# MOSFET.net
KiCad netlist of a schematic drawn in Altium Designer
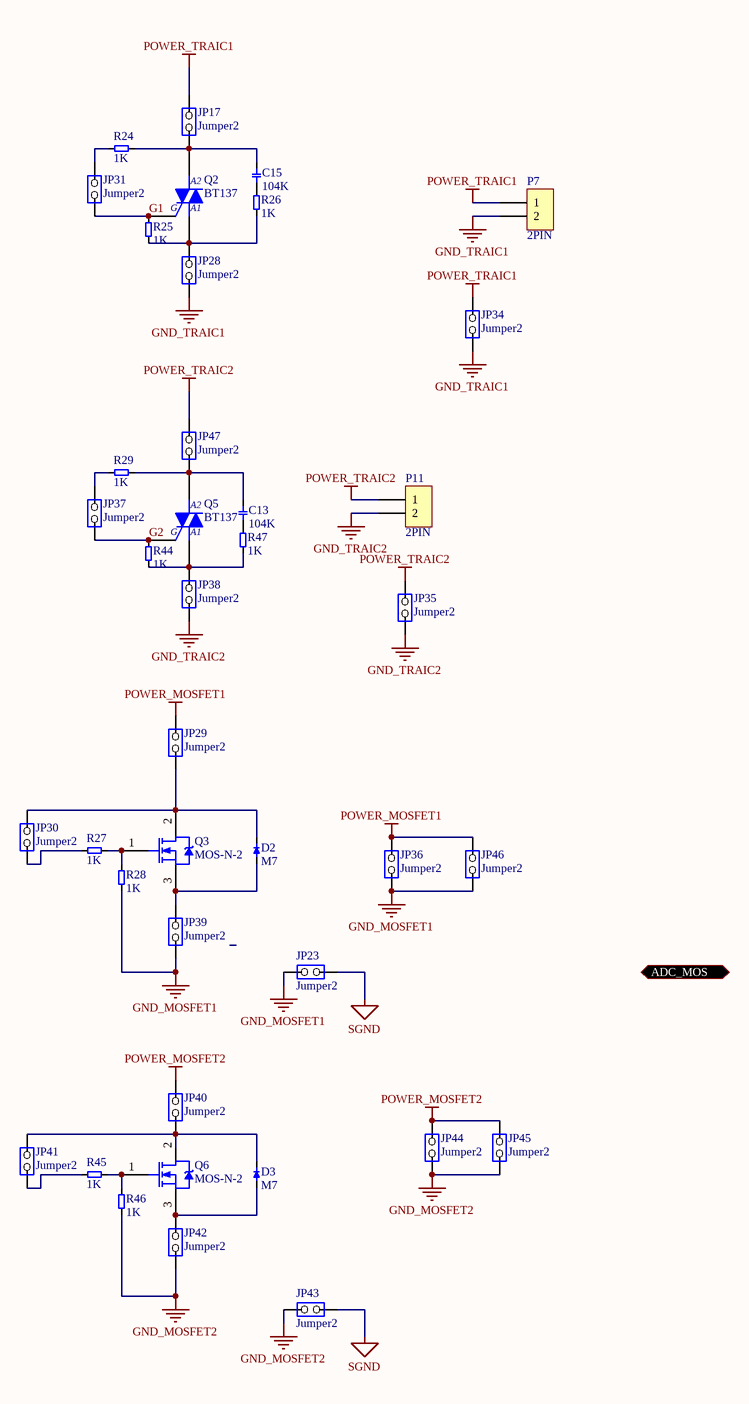
[diagram p0: 可控硅MOSFET.SchDoc]

(export (version "E")
  (design (tool "Eeschema 10.0.6"))
  (components
    (comp (ref "C13")
      (value "104K")
      (footprint "方形P15T6L18H12")
      (description "电容")
      (fields (field (name "PUBLISHER") "Altium Limited"))
      (libsource (lib "Miscellaneous Devices") (part "Cap"))
    )
    (comp (ref "C15")
      (value "104K")
      (footprint "方形P15T6L18H12")
      (description "电容")
      (fields (field (name "PUBLISHER") "Altium Limited"))
      (libsource (lib "Miscellaneous Devices") (part "Cap"))
    )
    (comp (ref "D2")
      (value "M7")
      (footprint "SMA")
      (description "二极管")
      (fields (field (name "PUBLISHER") "Altium Limited"))
      (libsource (lib "Miscellaneous Devices") (part "Diode"))
    )
    (comp (ref "D3")
      (value "M7")
      (footprint "SMA")
      (description "二极管")
      (fields (field (name "PUBLISHER") "Altium Limited"))
      (libsource (lib "Miscellaneous Devices") (part "Diode"))
    )
    (comp (ref "JP17")
      (value "Jumper2")
      (footprint "CON2-P2.54")
      (libsource (lib "Miscellaneous Connectors") (part "Jumper2"))
    )
    (comp (ref "JP23")
      (value "Jumper2")
      (footprint "CON2-P2.54")
      (libsource (lib "Miscellaneous Connectors") (part "Jumper2"))
    )
    (comp (ref "JP28")
      (value "Jumper2")
      (footprint "CON2-P2.54")
      (libsource (lib "Miscellaneous Connectors") (part "Jumper2"))
    )
    (comp (ref "JP29")
      (value "Jumper2")
      (footprint "CON2-P2.54")
      (libsource (lib "Miscellaneous Connectors") (part "Jumper2"))
    )
    (comp (ref "JP30")
      (value "Jumper2")
      (footprint "CON2-P2.54")
      (libsource (lib "Miscellaneous Connectors") (part "Jumper2"))
    )
    (comp (ref "JP31")
      (value "Jumper2")
      (footprint "CON2-P2.54")
      (libsource (lib "Miscellaneous Connectors") (part "Jumper2"))
    )
    (comp (ref "JP34")
      (value "Jumper2")
      (footprint "CON2-P2.54")
      (libsource (lib "Miscellaneous Connectors") (part "Jumper2"))
    )
    (comp (ref "JP35")
      (value "Jumper2")
      (footprint "CON2-P2.54")
      (libsource (lib "Miscellaneous Connectors") (part "Jumper2"))
    )
    (comp (ref "JP36")
      (value "Jumper2")
      (footprint "CON2-P2.54")
      (libsource (lib "Miscellaneous Connectors") (part "Jumper2"))
    )
    (comp (ref "JP37")
      (value "Jumper2")
      (footprint "CON2-P2.54")
      (libsource (lib "Miscellaneous Connectors") (part "Jumper2"))
    )
    (comp (ref "JP38")
      (value "Jumper2")
      (footprint "CON2-P2.54")
      (libsource (lib "Miscellaneous Connectors") (part "Jumper2"))
    )
    (comp (ref "JP39")
      (value "Jumper2")
      (footprint "CON2-P2.54")
      (libsource (lib "Miscellaneous Connectors") (part "Jumper2"))
    )
    (comp (ref "JP40")
      (value "Jumper2")
      (footprint "CON2-P2.54")
      (libsource (lib "Miscellaneous Connectors") (part "Jumper2"))
    )
    (comp (ref "JP41")
      (value "Jumper2")
      (footprint "CON2-P2.54")
      (libsource (lib "Miscellaneous Connectors") (part "Jumper2"))
    )
    (comp (ref "JP42")
      (value "Jumper2")
      (footprint "CON2-P2.54")
      (libsource (lib "Miscellaneous Connectors") (part "Jumper2"))
    )
    (comp (ref "JP43")
      (value "Jumper2")
      (footprint "CON2-P2.54")
      (libsource (lib "Miscellaneous Connectors") (part "Jumper2"))
    )
    (comp (ref "JP44")
      (value "Jumper2")
      (footprint "CON2-P2.54")
      (libsource (lib "Miscellaneous Connectors") (part "Jumper2"))
    )
    (comp (ref "JP45")
      (value "Jumper2")
      (footprint "CON2-P2.54")
      (libsource (lib "Miscellaneous Connectors") (part "Jumper2"))
    )
    (comp (ref "JP46")
      (value "Jumper2")
      (footprint "CON2-P2.54")
      (libsource (lib "Miscellaneous Connectors") (part "Jumper2"))
    )
    (comp (ref "JP47")
      (value "Jumper2")
      (footprint "CON2-P2.54")
      (libsource (lib "Miscellaneous Connectors") (part "Jumper2"))
    )
    (comp (ref "P7")
      (value "2PIN")
      (footprint "CON2-P3.96(VH)")
      (description "连接器")
      (fields (field (name "PUBLISHER") "Altium Limited"))
      (libsource (lib "Miscellaneous Connectors") (part "Header 2"))
    )
    (comp (ref "P11")
      (value "2PIN")
      (footprint "CON2-P3.96(VH)")
      (description "连接器")
      (fields (field (name "PUBLISHER") "Altium Limited"))
      (libsource (lib "Miscellaneous Connectors") (part "Header 2"))
    )
    (comp (ref "Q2")
      (value "BT137")
      (footprint "TO-252-2L")
      (description "可控硅")
      (fields (field (name "PUBLISHER") "Altium Limited"))
      (libsource (lib "Miscellaneous Devices") (part "Triac"))
    )
    (comp (ref "Q3")
      (value "MOS-N-2")
      (footprint "TO-252-2L")
      (description "N-Channel Power MOSFET")
      (fields (field (name "PUBLISHER") "Altium Limited"))
      (libsource (lib "Miscellaneous Devices") (part "MOS-N-2"))
    )
    (comp (ref "Q5")
      (value "BT137")
      (footprint "TO-252-2L")
      (description "可控硅")
      (fields (field (name "PUBLISHER") "Altium Limited"))
      (libsource (lib "Miscellaneous Devices") (part "Triac"))
    )
    (comp (ref "Q6")
      (value "MOS-N-2")
      (footprint "TO-252-2L")
      (description "N-Channel Power MOSFET")
      (fields (field (name "PUBLISHER") "Altium Limited"))
      (libsource (lib "Miscellaneous Devices") (part "MOS-N-2"))
    )
    (comp (ref "R24")
      (value "1K")
      (footprint "1206")
      (description "电阻")
      (fields (field (name "PUBLISHER") "Altium Limited"))
      (libsource (lib "Miscellaneous Devices") (part "Res1"))
    )
    (comp (ref "R25")
      (value "1K")
      (footprint "1206")
      (description "电阻")
      (fields (field (name "PUBLISHER") "Altium Limited"))
      (libsource (lib "Miscellaneous Devices") (part "Res1"))
    )
    (comp (ref "R26")
      (value "1K")
      (footprint "1206")
      (description "电阻")
      (fields (field (name "PUBLISHER") "Altium Limited"))
      (libsource (lib "Miscellaneous Devices") (part "Res1"))
    )
    (comp (ref "R27")
      (value "1K")
      (footprint "1206")
      (description "电阻")
      (fields (field (name "PUBLISHER") "Altium Limited"))
      (libsource (lib "Miscellaneous Devices") (part "Res1"))
    )
    (comp (ref "R28")
      (value "1K")
      (footprint "1206")
      (description "电阻")
      (fields (field (name "PUBLISHER") "Altium Limited"))
      (libsource (lib "Miscellaneous Devices") (part "Res1"))
    )
    (comp (ref "R29")
      (value "1K")
      (footprint "1206")
      (description "电阻")
      (fields (field (name "PUBLISHER") "Altium Limited"))
      (libsource (lib "Miscellaneous Devices") (part "Res1"))
    )
    (comp (ref "R44")
      (value "1K")
      (footprint "1206")
      (description "电阻")
      (fields (field (name "PUBLISHER") "Altium Limited"))
      (libsource (lib "Miscellaneous Devices") (part "Res1"))
    )
    (comp (ref "R45")
      (value "1K")
      (footprint "1206")
      (description "电阻")
      (fields (field (name "PUBLISHER") "Altium Limited"))
      (libsource (lib "Miscellaneous Devices") (part "Res1"))
    )
    (comp (ref "R46")
      (value "1K")
      (footprint "1206")
      (description "电阻")
      (fields (field (name "PUBLISHER") "Altium Limited"))
      (libsource (lib "Miscellaneous Devices") (part "Res1"))
    )
    (comp (ref "R47")
      (value "1K")
      (footprint "1206")
      (description "电阻")
      (fields (field (name "PUBLISHER") "Altium Limited"))
      (libsource (lib "Miscellaneous Devices") (part "Res1"))
    )
  )
  (nets
    (net (code "2") (name "/G1") (class "Default")
      (node (ref "JP31") (pin "1") (pinfunction "COMMON_1") (pintype "passive"))
      (node (ref "Q2") (pin "3") (pinfunction "G_3") (pintype "passive"))
      (node (ref "R25") (pin "2") (pinfunction "2_2") (pintype "passive"))
    )
    (net (code "3") (name "/G2") (class "Default")
      (node (ref "JP37") (pin "1") (pinfunction "COMMON_1") (pintype "passive"))
      (node (ref "Q5") (pin "3") (pinfunction "G_3") (pintype "passive"))
      (node (ref "R44") (pin "2") (pinfunction "2_2") (pintype "passive"))
    )
    (net (code "4") (name "GND_MOSFET1") (class "Default")
      (node (ref "JP23") (pin "2") (pinfunction "NO_2") (pintype "passive"))
      (node (ref "JP36") (pin "1") (pinfunction "COMMON_1") (pintype "passive"))
      (node (ref "JP39") (pin "1") (pinfunction "COMMON_1") (pintype "passive"))
      (node (ref "JP46") (pin "1") (pinfunction "COMMON_1") (pintype "passive"))
      (node (ref "R28") (pin "2") (pinfunction "2_2") (pintype "passive"))
    )
    (net (code "5") (name "GND_MOSFET2") (class "Default")
      (node (ref "JP42") (pin "1") (pinfunction "COMMON_1") (pintype "passive"))
      (node (ref "JP43") (pin "2") (pinfunction "NO_2") (pintype "passive"))
      (node (ref "JP44") (pin "1") (pinfunction "COMMON_1") (pintype "passive"))
      (node (ref "JP45") (pin "1") (pinfunction "COMMON_1") (pintype "passive"))
      (node (ref "R46") (pin "2") (pinfunction "2_2") (pintype "passive"))
    )
    (net (code "6") (name "GND_TRAIC1") (class "Default")
      (node (ref "JP28") (pin "1") (pinfunction "COMMON_1") (pintype "passive"))
      (node (ref "JP34") (pin "1") (pinfunction "COMMON_1") (pintype "passive"))
      (node (ref "P7") (pin "2") (pinfunction "2_2") (pintype "passive"))
    )
    (net (code "7") (name "GND_TRAIC2") (class "Default")
      (node (ref "JP35") (pin "1") (pinfunction "COMMON_1") (pintype "passive"))
      (node (ref "JP38") (pin "1") (pinfunction "COMMON_1") (pintype "passive"))
      (node (ref "P11") (pin "2") (pinfunction "2_2") (pintype "passive"))
    )
    (net (code "8") (name "Net-(C13-Pad1)") (class "Default")
      (node (ref "C13") (pin "1") (pinfunction "1_1") (pintype "passive"))
      (node (ref "R47") (pin "2") (pinfunction "2_2") (pintype "passive"))
    )
    (net (code "9") (name "Net-(C15-Pad1)") (class "Default")
      (node (ref "C15") (pin "1") (pinfunction "1_1") (pintype "passive"))
      (node (ref "R26") (pin "2") (pinfunction "2_2") (pintype "passive"))
    )
    (net (code "10") (name "Net-(JP17-COMMON)") (class "Default")
      (node (ref "C15") (pin "2") (pinfunction "2_2") (pintype "passive"))
      (node (ref "JP17") (pin "1") (pinfunction "COMMON_1") (pintype "passive"))
      (node (ref "Q2") (pin "2") (pinfunction "A2_2") (pintype "passive"))
      (node (ref "R24") (pin "2") (pinfunction "2_2") (pintype "passive"))
    )
    (net (code "11") (name "Net-(JP28-NO)") (class "Default")
      (node (ref "JP28") (pin "2") (pinfunction "NO_2") (pintype "passive"))
      (node (ref "Q2") (pin "1") (pinfunction "A1_1") (pintype "passive"))
      (node (ref "R25") (pin "1") (pinfunction "1_1") (pintype "passive"))
      (node (ref "R26") (pin "1") (pinfunction "1_1") (pintype "passive"))
    )
    (net (code "12") (name "Net-(JP29-COMMON)") (class "Default")
      (node (ref "D2") (pin "1") (pinfunction "1_1") (pintype "passive"))
      (node (ref "JP29") (pin "1") (pinfunction "COMMON_1") (pintype "passive"))
      (node (ref "JP30") (pin "2") (pinfunction "NO_2") (pintype "passive"))
      (node (ref "Q3") (pin "2") (pinfunction "D_2") (pintype "passive"))
    )
    (net (code "13") (name "Net-(JP30-COMMON)") (class "Default")
      (node (ref "JP30") (pin "1") (pinfunction "COMMON_1") (pintype "passive"))
      (node (ref "R27") (pin "2") (pinfunction "2_2") (pintype "passive"))
    )
    (net (code "14") (name "Net-(JP31-NO)") (class "Default")
      (node (ref "JP31") (pin "2") (pinfunction "NO_2") (pintype "passive"))
      (node (ref "R24") (pin "1") (pinfunction "1_1") (pintype "passive"))
    )
    (net (code "15") (name "Net-(JP37-NO)") (class "Default")
      (node (ref "JP37") (pin "2") (pinfunction "NO_2") (pintype "passive"))
      (node (ref "R29") (pin "1") (pinfunction "1_1") (pintype "passive"))
    )
    (net (code "16") (name "Net-(JP38-NO)") (class "Default")
      (node (ref "JP38") (pin "2") (pinfunction "NO_2") (pintype "passive"))
      (node (ref "Q5") (pin "1") (pinfunction "A1_1") (pintype "passive"))
      (node (ref "R44") (pin "1") (pinfunction "1_1") (pintype "passive"))
      (node (ref "R47") (pin "1") (pinfunction "1_1") (pintype "passive"))
    )
    (net (code "17") (name "Net-(JP39-NO)") (class "Default")
      (node (ref "D2") (pin "2") (pinfunction "2_2") (pintype "passive"))
      (node (ref "JP39") (pin "2") (pinfunction "NO_2") (pintype "passive"))
      (node (ref "Q3") (pin "3") (pinfunction "S_3") (pintype "passive"))
    )
    (net (code "18") (name "Net-(JP40-COMMON)") (class "Default")
      (node (ref "D3") (pin "1") (pinfunction "1_1") (pintype "passive"))
      (node (ref "JP40") (pin "1") (pinfunction "COMMON_1") (pintype "passive"))
      (node (ref "JP41") (pin "2") (pinfunction "NO_2") (pintype "passive"))
      (node (ref "Q6") (pin "2") (pinfunction "D_2") (pintype "passive"))
    )
    (net (code "19") (name "Net-(JP41-COMMON)") (class "Default")
      (node (ref "JP41") (pin "1") (pinfunction "COMMON_1") (pintype "passive"))
      (node (ref "R45") (pin "2") (pinfunction "2_2") (pintype "passive"))
    )
    (net (code "20") (name "Net-(JP42-NO)") (class "Default")
      (node (ref "D3") (pin "2") (pinfunction "2_2") (pintype "passive"))
      (node (ref "JP42") (pin "2") (pinfunction "NO_2") (pintype "passive"))
      (node (ref "Q6") (pin "3") (pinfunction "S_3") (pintype "passive"))
    )
    (net (code "21") (name "Net-(JP47-COMMON)") (class "Default")
      (node (ref "C13") (pin "2") (pinfunction "2_2") (pintype "passive"))
      (node (ref "JP47") (pin "1") (pinfunction "COMMON_1") (pintype "passive"))
      (node (ref "Q5") (pin "2") (pinfunction "A2_2") (pintype "passive"))
      (node (ref "R29") (pin "2") (pinfunction "2_2") (pintype "passive"))
    )
    (net (code "22") (name "Net-(Q3-G)") (class "Default")
      (node (ref "Q3") (pin "1") (pinfunction "G_1") (pintype "passive"))
      (node (ref "R27") (pin "1") (pinfunction "1_1") (pintype "passive"))
      (node (ref "R28") (pin "1") (pinfunction "1_1") (pintype "passive"))
    )
    (net (code "23") (name "Net-(Q6-G)") (class "Default")
      (node (ref "Q6") (pin "1") (pinfunction "G_1") (pintype "passive"))
      (node (ref "R45") (pin "1") (pinfunction "1_1") (pintype "passive"))
      (node (ref "R46") (pin "1") (pinfunction "1_1") (pintype "passive"))
    )
    (net (code "24") (name "POWER_MOSFET1") (class "Default")
      (node (ref "JP29") (pin "2") (pinfunction "NO_2") (pintype "passive"))
      (node (ref "JP36") (pin "2") (pinfunction "NO_2") (pintype "passive"))
      (node (ref "JP46") (pin "2") (pinfunction "NO_2") (pintype "passive"))
    )
    (net (code "25") (name "POWER_MOSFET2") (class "Default")
      (node (ref "JP40") (pin "2") (pinfunction "NO_2") (pintype "passive"))
      (node (ref "JP44") (pin "2") (pinfunction "NO_2") (pintype "passive"))
      (node (ref "JP45") (pin "2") (pinfunction "NO_2") (pintype "passive"))
    )
    (net (code "26") (name "POWER_TRAIC1") (class "Default")
      (node (ref "JP17") (pin "2") (pinfunction "NO_2") (pintype "passive"))
      (node (ref "JP34") (pin "2") (pinfunction "NO_2") (pintype "passive"))
      (node (ref "P7") (pin "1") (pinfunction "1_1") (pintype "passive"))
    )
    (net (code "27") (name "POWER_TRAIC2") (class "Default")
      (node (ref "JP35") (pin "2") (pinfunction "NO_2") (pintype "passive"))
      (node (ref "JP47") (pin "2") (pinfunction "NO_2") (pintype "passive"))
      (node (ref "P11") (pin "1") (pinfunction "1_1") (pintype "passive"))
    )
    (net (code "28") (name "SGND") (class "Default")
      (node (ref "JP23") (pin "1") (pinfunction "COMMON_1") (pintype "passive"))
      (node (ref "JP43") (pin "1") (pinfunction "COMMON_1") (pintype "passive"))
    )
  )
)
